# 201_GridPos2.net
KiCad netlist of a schematic drawn in Altium Designer
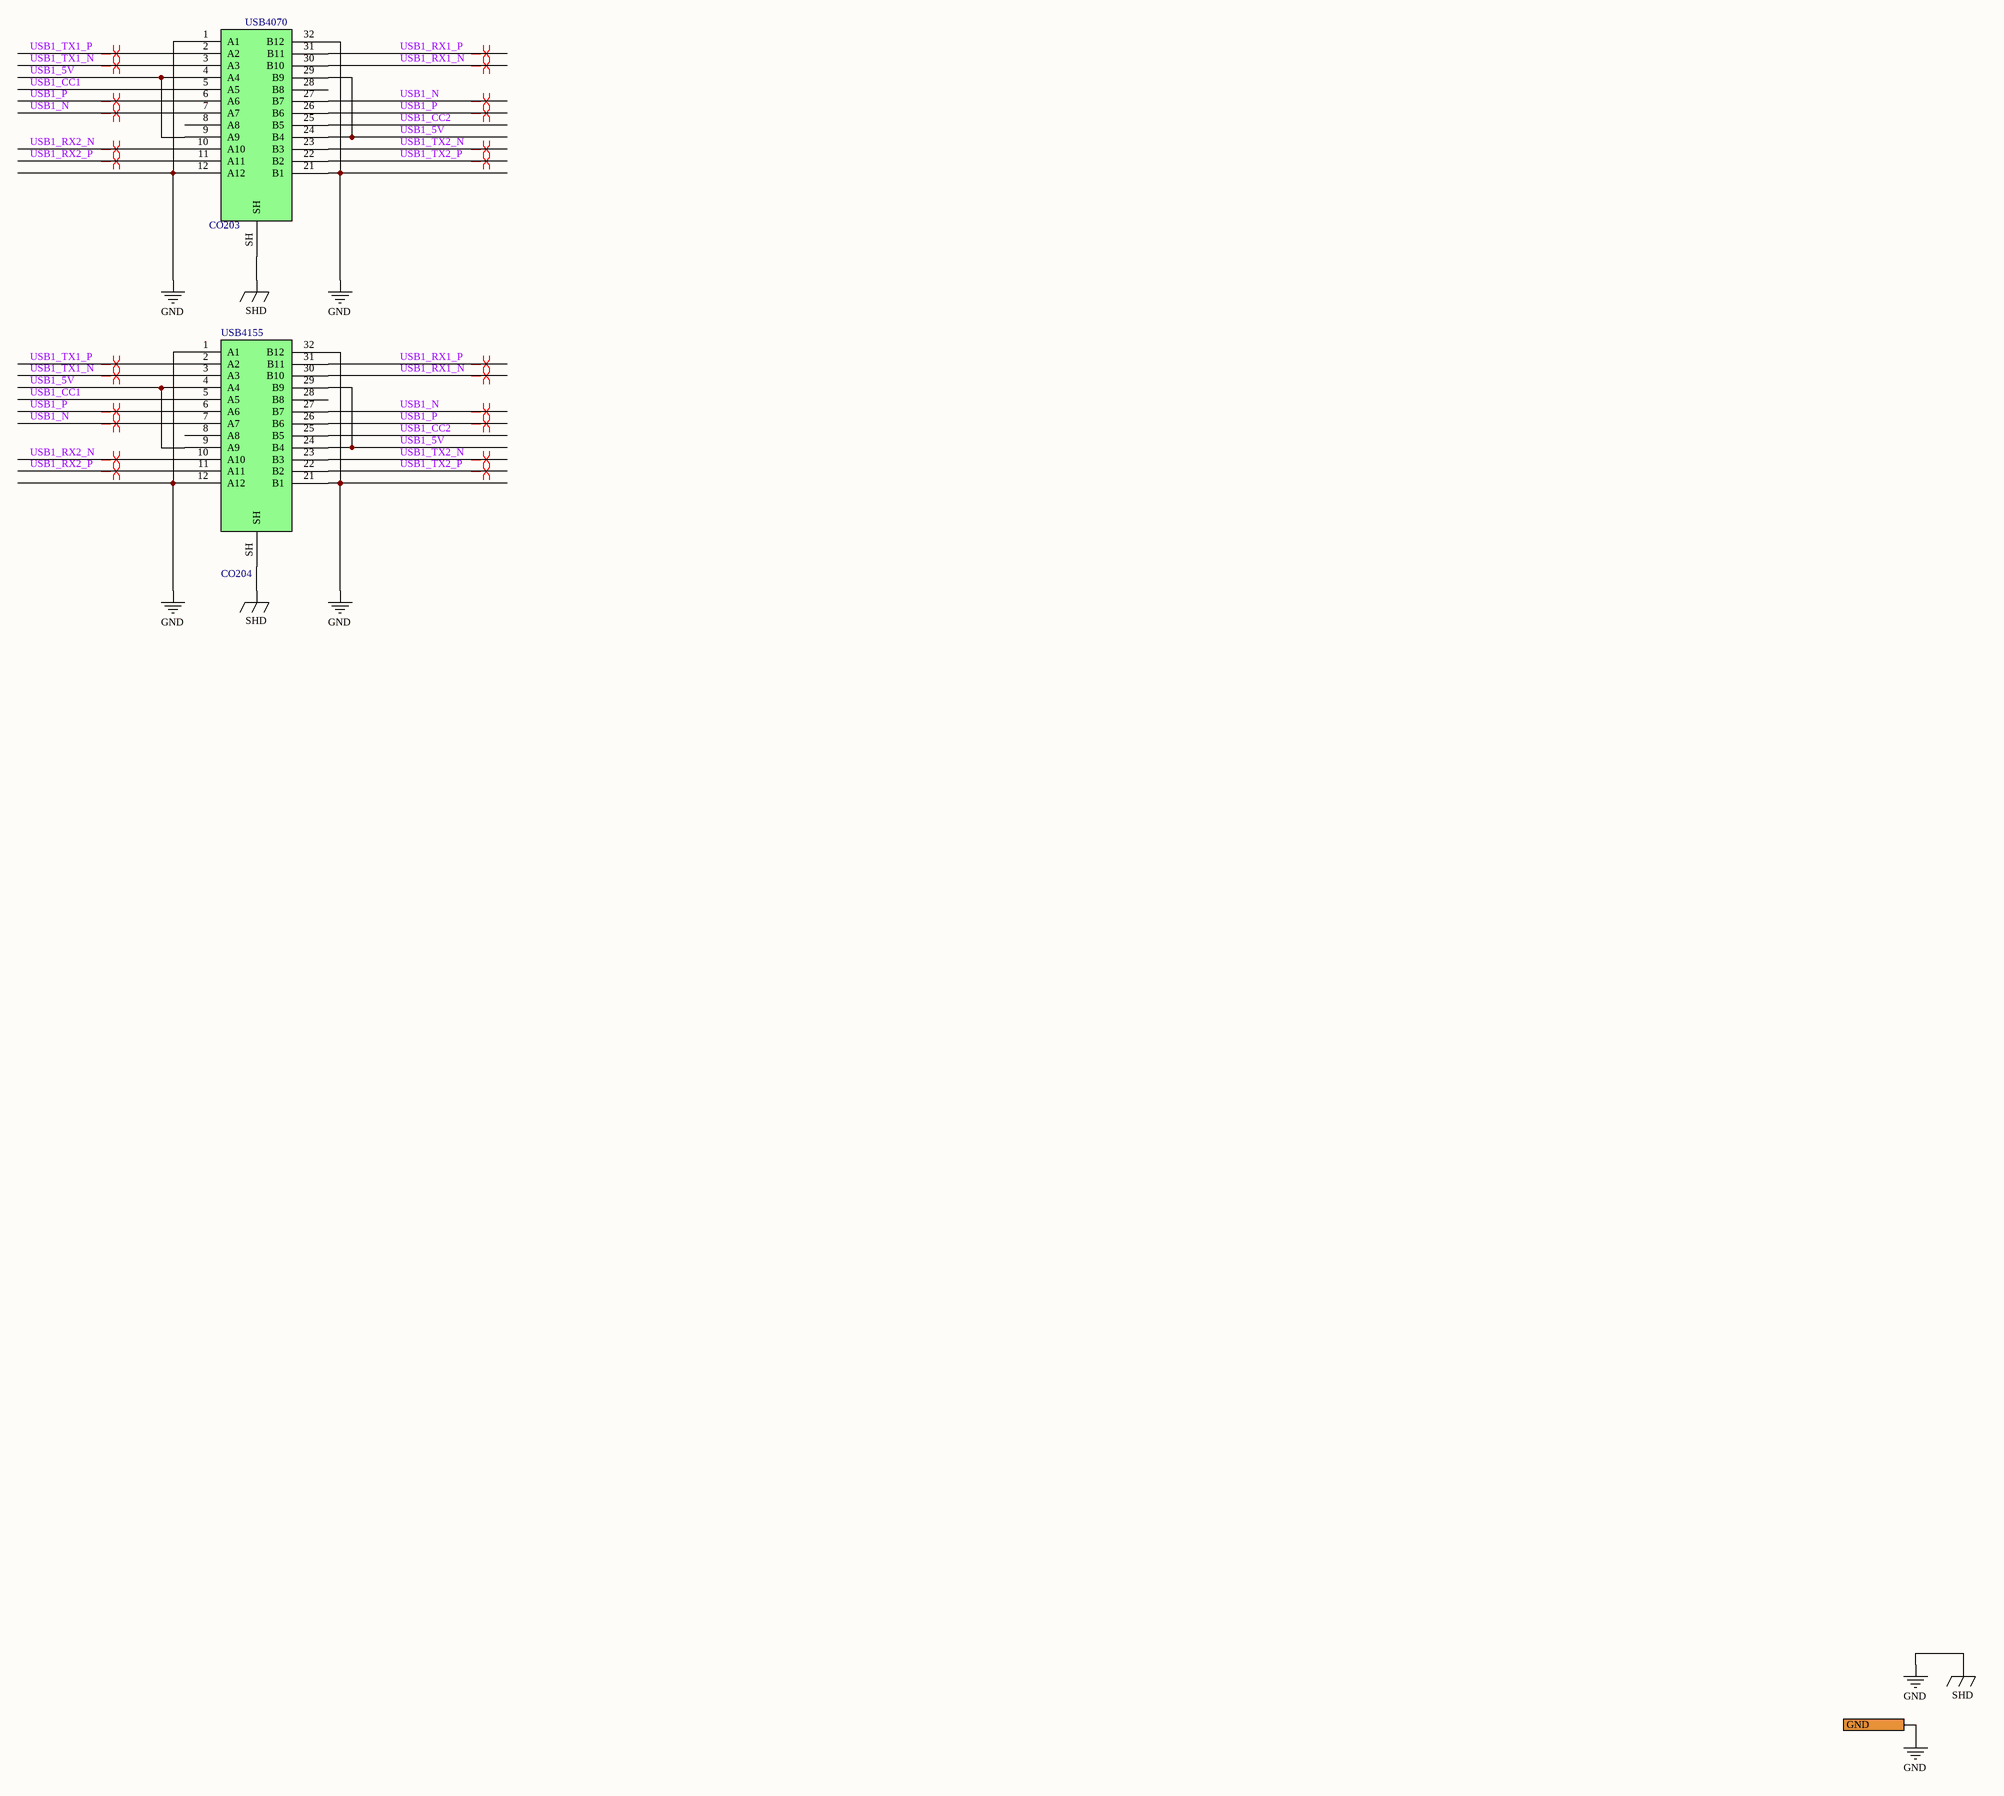
[diagram p0: 201_GridPos2.SchDoc]

(export (version "E")
  (design (tool "Eeschema 10.0.6"))
  (components
    (comp (ref "CO203")
      (value "USB4070")
      (footprint "USB4070-30-C")
      (description "USB C connector Receptacle Vertical")
      (fields
        (field (name "REFVAL") "USB4070")
        (field (name "PART NUMBER") "CO0021")
        (field (name "MANFACTPART") "USB4070-30-C")
      )
      (libsource (lib "GTS_Database") (part "USB-CC"))
    )
    (comp (ref "CO204")
      (value "USB4155")
      (footprint "USB4155-03-C")
      (description "USB C connector Plug Horizontal")
      (fields
        (field (name "REFVAL") "USB4155")
        (field (name "PART NUMBER") "CO0031")
        (field (name "MANFACTPART") "USB4155-03-C")
      )
      (libsource (lib "GTS_Database") (part "USB-CC"))
    )
  )
  (nets
    (net (code "1") (name "/USB1_5V") (class "Default")
      (node (ref "CO203") (pin "24") (pinfunction "B4_24") (pintype "passive"))
      (node (ref "CO203") (pin "29") (pinfunction "B9_29") (pintype "passive"))
      (node (ref "CO203") (pin "4") (pinfunction "A4_4") (pintype "passive"))
      (node (ref "CO203") (pin "9") (pinfunction "A9_9") (pintype "passive"))
      (node (ref "CO204") (pin "24") (pinfunction "B4_24") (pintype "passive"))
      (node (ref "CO204") (pin "29") (pinfunction "B9_29") (pintype "passive"))
      (node (ref "CO204") (pin "4") (pinfunction "A4_4") (pintype "passive"))
      (node (ref "CO204") (pin "9") (pinfunction "A9_9") (pintype "passive"))
    )
    (net (code "2") (name "/USB1_CC1") (class "Default")
      (node (ref "CO203") (pin "5") (pinfunction "A5_5") (pintype "passive"))
      (node (ref "CO204") (pin "5") (pinfunction "A5_5") (pintype "passive"))
    )
    (net (code "3") (name "/USB1_CC2") (class "Default")
      (node (ref "CO203") (pin "25") (pinfunction "B5_25") (pintype "passive"))
      (node (ref "CO204") (pin "25") (pinfunction "B5_25") (pintype "passive"))
    )
    (net (code "4") (name "/USB1_N") (class "Default")
      (node (ref "CO203") (pin "27") (pinfunction "B7_27") (pintype "passive"))
      (node (ref "CO203") (pin "7") (pinfunction "A7_7") (pintype "passive"))
      (node (ref "CO204") (pin "27") (pinfunction "B7_27") (pintype "passive"))
      (node (ref "CO204") (pin "7") (pinfunction "A7_7") (pintype "passive"))
    )
    (net (code "5") (name "/USB1_P") (class "Default")
      (node (ref "CO203") (pin "26") (pinfunction "B6_26") (pintype "passive"))
      (node (ref "CO203") (pin "6") (pinfunction "A6_6") (pintype "passive"))
      (node (ref "CO204") (pin "26") (pinfunction "B6_26") (pintype "passive"))
      (node (ref "CO204") (pin "6") (pinfunction "A6_6") (pintype "passive"))
    )
    (net (code "6") (name "/USB1_RX1_N") (class "Default")
      (node (ref "CO203") (pin "30") (pinfunction "B10_30") (pintype "passive"))
      (node (ref "CO204") (pin "30") (pinfunction "B10_30") (pintype "passive"))
    )
    (net (code "7") (name "/USB1_RX1_P") (class "Default")
      (node (ref "CO203") (pin "31") (pinfunction "B11_31") (pintype "passive"))
      (node (ref "CO204") (pin "31") (pinfunction "B11_31") (pintype "passive"))
    )
    (net (code "8") (name "/USB1_RX2_N") (class "Default")
      (node (ref "CO203") (pin "10") (pinfunction "A10_10") (pintype "passive"))
      (node (ref "CO204") (pin "10") (pinfunction "A10_10") (pintype "passive"))
    )
    (net (code "9") (name "/USB1_RX2_P") (class "Default")
      (node (ref "CO203") (pin "11") (pinfunction "A11_11") (pintype "passive"))
      (node (ref "CO204") (pin "11") (pinfunction "A11_11") (pintype "passive"))
    )
    (net (code "10") (name "/USB1_TX1_N") (class "Default")
      (node (ref "CO203") (pin "3") (pinfunction "A3_3") (pintype "passive"))
      (node (ref "CO204") (pin "3") (pinfunction "A3_3") (pintype "passive"))
    )
    (net (code "11") (name "/USB1_TX1_P") (class "Default")
      (node (ref "CO203") (pin "2") (pinfunction "A2_2") (pintype "passive"))
      (node (ref "CO204") (pin "2") (pinfunction "A2_2") (pintype "passive"))
    )
    (net (code "12") (name "/USB1_TX2_N") (class "Default")
      (node (ref "CO203") (pin "23") (pinfunction "B3_23") (pintype "passive"))
      (node (ref "CO204") (pin "23") (pinfunction "B3_23") (pintype "passive"))
    )
    (net (code "13") (name "/USB1_TX2_P") (class "Default")
      (node (ref "CO203") (pin "22") (pinfunction "B2_22") (pintype "passive"))
      (node (ref "CO204") (pin "22") (pinfunction "B2_22") (pintype "passive"))
    )
    (net (code "14") (name "GND") (class "Default")
      (node (ref "CO203") (pin "1") (pinfunction "A1_1") (pintype "passive"))
      (node (ref "CO203") (pin "12") (pinfunction "A12_12") (pintype "passive"))
      (node (ref "CO203") (pin "21") (pinfunction "B1_21") (pintype "passive"))
      (node (ref "CO203") (pin "32") (pinfunction "B12_32") (pintype "passive"))
      (node (ref "CO203") (pin "SH") (pinfunction "SH_SH") (pintype "power_in"))
      (node (ref "CO204") (pin "1") (pinfunction "A1_1") (pintype "passive"))
      (node (ref "CO204") (pin "12") (pinfunction "A12_12") (pintype "passive"))
      (node (ref "CO204") (pin "21") (pinfunction "B1_21") (pintype "passive"))
      (node (ref "CO204") (pin "32") (pinfunction "B12_32") (pintype "passive"))
      (node (ref "CO204") (pin "SH") (pinfunction "SH_SH") (pintype "power_in"))
    )
    (net (code "15") (name "unconnected-(CO203-A8-Pad8)") (class "Default")
      (node (ref "CO203") (pin "8") (pinfunction "A8_8") (pintype "passive"))
    )
    (net (code "16") (name "unconnected-(CO203-B8-Pad28)") (class "Default")
      (node (ref "CO203") (pin "28") (pinfunction "B8_28") (pintype "passive"))
    )
    (net (code "17") (name "unconnected-(CO204-A8-Pad8)") (class "Default")
      (node (ref "CO204") (pin "8") (pinfunction "A8_8") (pintype "passive"))
    )
    (net (code "18") (name "unconnected-(CO204-B8-Pad28)") (class "Default")
      (node (ref "CO204") (pin "28") (pinfunction "B8_28") (pintype "passive"))
    )
  )
)
